# FPGA.net
KiCad netlist of a schematic drawn in Altium Designer
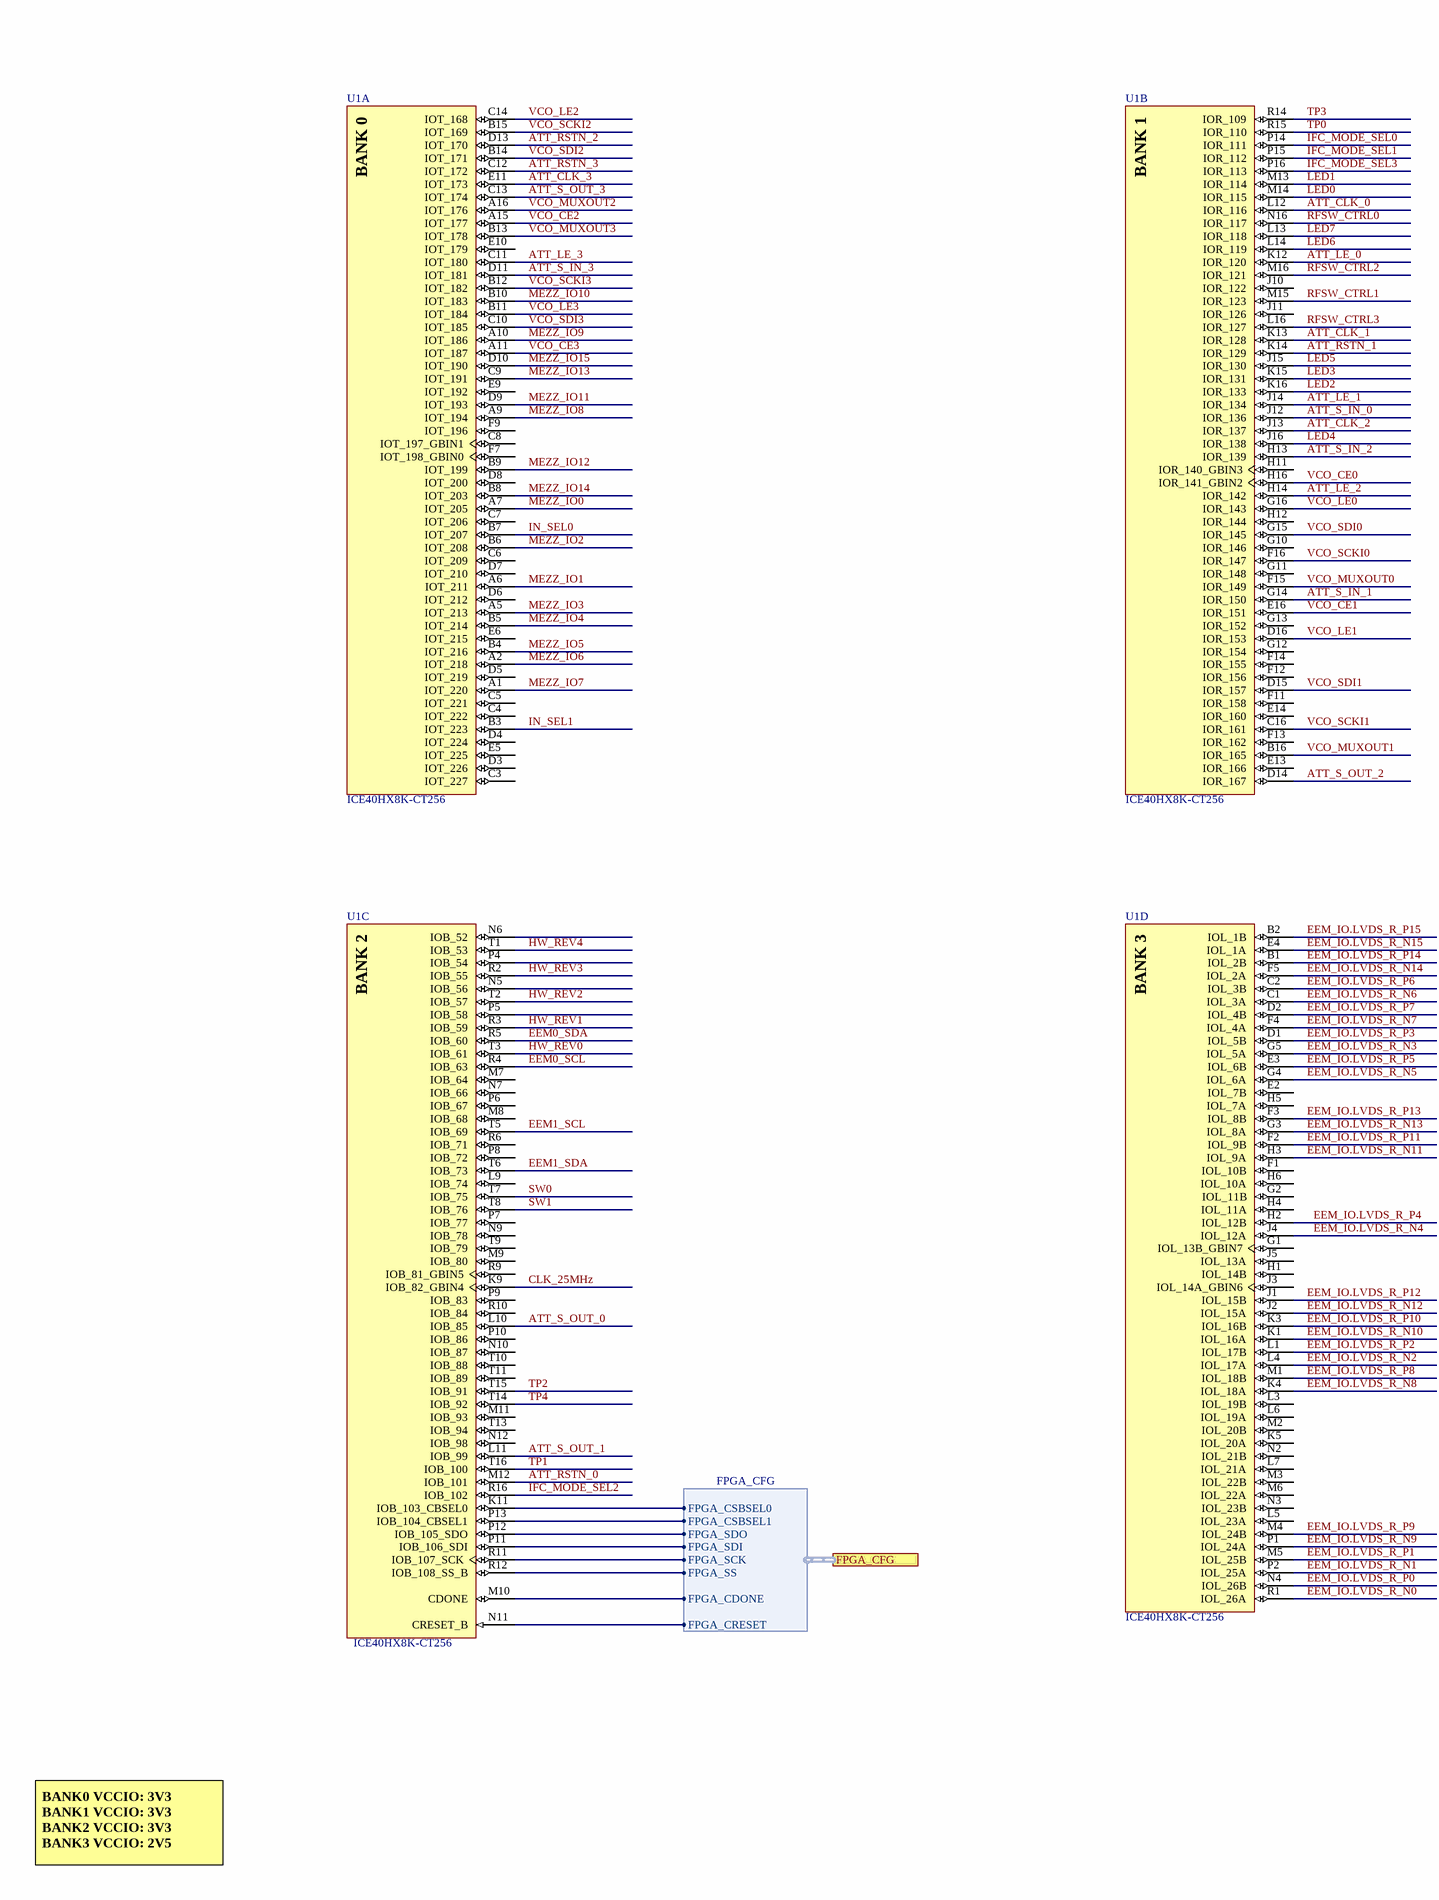
[diagram p0: FPGA.SchDoc, left]
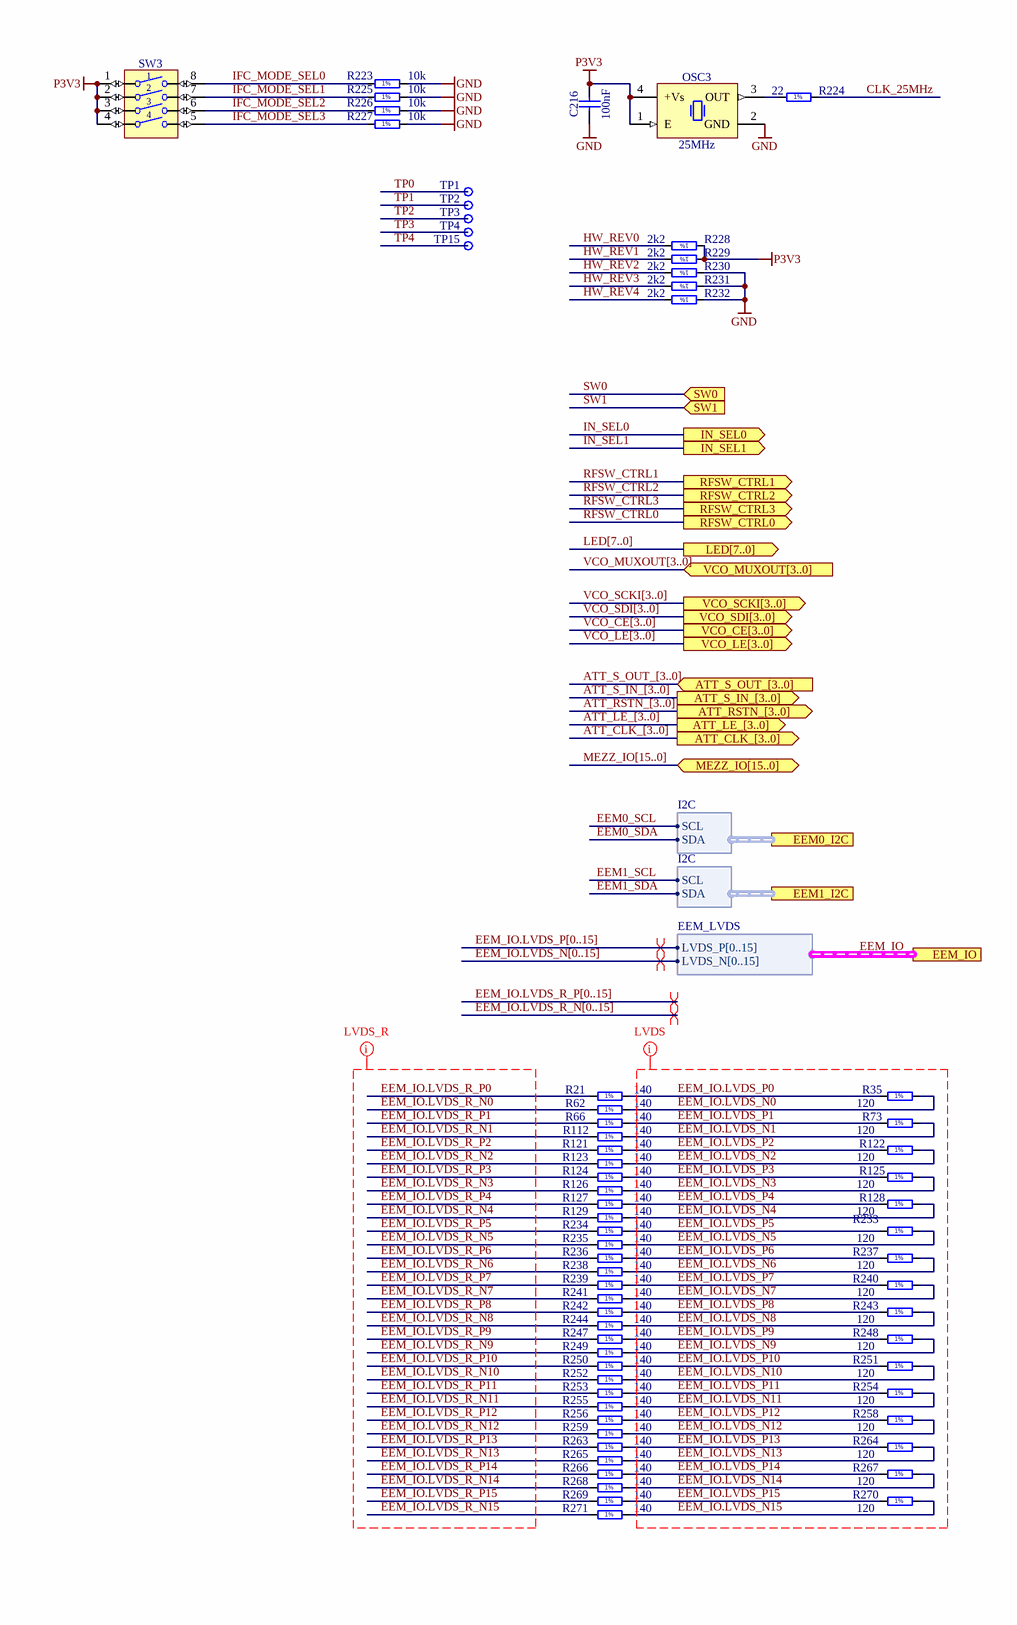
[diagram p1: FPGA.SchDoc, right]

(export (version "E")
  (design (tool "Eeschema 10.0.6"))
  (components
    (comp (ref "C216")
      (value "100nF")
      (footprint "CAPC1005X55N")
      (description "Non-polarised capacitor")
      (fields
        (field (name "PART NUMBER") "CC0402_100NF_16V_10%_X5R")
        (field (name "VOLTAGE") "16V")
        (field (name "AUTHOR") "CERN DEM JLC")
      )
      (libsource (lib "Capacitors") (part "Capacitor - non polarized"))
    )
    (comp (ref "OSC3")
      (value "25MHz")
      (footprint "OSC_IQD_CFPS-39")
      (description "Oscillator 4 pins 1=E 2=GND 3=OUT 4=+Vs")
      (fields
        (field (name "PART NUMBER") "OSC_25MHZ_IQD_LFSPXO025165")
        (field (name "MANUFACTURER") "IQD FREQUENCY PRODUCTS")
        (field (name "AUTHOR") "CERN DEM JLC")
      )
      (libsource (lib "ICs And Semiconductors") (part "Oscillator 1E 2GND 3OUT 4Vs"))
    )
    (comp (ref "R21")
      (value "140")
      (footprint "RESC0603X28N")
      (description "Resistor - 1%")
      (fields
        (field (name "PART NUMBER") "R0201_140R_1%_0.05W_200PPM")
        (field (name "POWER") "0.05W")
        (field (name "AUTHOR") "CERN DEM MR")
      )
      (libsource (lib "Resistors") (part "Resistor - 1%"))
    )
    (comp (ref "R35")
      (value "120")
      (footprint "RESC1005X40N")
      (description "Resistor - 1%")
      (fields
        (field (name "PART NUMBER") "R0402_120R_1%_0.0625W_100PPM")
        (field (name "POWER") "0.0625W")
        (field (name "AUTHOR") "CERN DEM JLC")
      )
      (libsource (lib "Resistors") (part "Resistor - 1%"))
    )
    (comp (ref "R62")
      (value "140")
      (footprint "RESC0603X28N")
      (description "Resistor - 1%")
      (fields
        (field (name "PART NUMBER") "R0201_140R_1%_0.05W_200PPM")
        (field (name "POWER") "0.05W")
        (field (name "AUTHOR") "CERN DEM MR")
      )
      (libsource (lib "Resistors") (part "Resistor - 1%"))
    )
    (comp (ref "R66")
      (value "140")
      (footprint "RESC0603X28N")
      (description "Resistor - 1%")
      (fields
        (field (name "PART NUMBER") "R0201_140R_1%_0.05W_200PPM")
        (field (name "POWER") "0.05W")
        (field (name "AUTHOR") "CERN DEM MR")
      )
      (libsource (lib "Resistors") (part "Resistor - 1%"))
    )
    (comp (ref "R73")
      (value "120")
      (footprint "RESC1005X40N")
      (description "Resistor - 1%")
      (fields
        (field (name "PART NUMBER") "R0402_120R_1%_0.0625W_100PPM")
        (field (name "POWER") "0.0625W")
        (field (name "AUTHOR") "CERN DEM JLC")
      )
      (libsource (lib "Resistors") (part "Resistor - 1%"))
    )
    (comp (ref "R112")
      (value "140")
      (footprint "RESC0603X28N")
      (description "Resistor - 1%")
      (fields
        (field (name "PART NUMBER") "R0201_140R_1%_0.05W_200PPM")
        (field (name "POWER") "0.05W")
        (field (name "AUTHOR") "CERN DEM MR")
      )
      (libsource (lib "Resistors") (part "Resistor - 1%"))
    )
    (comp (ref "R121")
      (value "140")
      (footprint "RESC0603X28N")
      (description "Resistor - 1%")
      (fields
        (field (name "PART NUMBER") "R0201_140R_1%_0.05W_200PPM")
        (field (name "POWER") "0.05W")
        (field (name "AUTHOR") "CERN DEM MR")
      )
      (libsource (lib "Resistors") (part "Resistor - 1%"))
    )
    (comp (ref "R122")
      (value "120")
      (footprint "RESC1005X40N")
      (description "Resistor - 1%")
      (fields
        (field (name "PART NUMBER") "R0402_120R_1%_0.0625W_100PPM")
        (field (name "POWER") "0.0625W")
        (field (name "AUTHOR") "CERN DEM JLC")
      )
      (libsource (lib "Resistors") (part "Resistor - 1%"))
    )
    (comp (ref "R123")
      (value "140")
      (footprint "RESC0603X28N")
      (description "Resistor - 1%")
      (fields
        (field (name "PART NUMBER") "R0201_140R_1%_0.05W_200PPM")
        (field (name "POWER") "0.05W")
        (field (name "AUTHOR") "CERN DEM MR")
      )
      (libsource (lib "Resistors") (part "Resistor - 1%"))
    )
    (comp (ref "R124")
      (value "140")
      (footprint "RESC0603X28N")
      (description "Resistor - 1%")
      (fields
        (field (name "PART NUMBER") "R0201_140R_1%_0.05W_200PPM")
        (field (name "POWER") "0.05W")
        (field (name "AUTHOR") "CERN DEM MR")
      )
      (libsource (lib "Resistors") (part "Resistor - 1%"))
    )
    (comp (ref "R125")
      (value "120")
      (footprint "RESC1005X40N")
      (description "Resistor - 1%")
      (fields
        (field (name "PART NUMBER") "R0402_120R_1%_0.0625W_100PPM")
        (field (name "POWER") "0.0625W")
        (field (name "AUTHOR") "CERN DEM JLC")
      )
      (libsource (lib "Resistors") (part "Resistor - 1%"))
    )
    (comp (ref "R126")
      (value "140")
      (footprint "RESC0603X28N")
      (description "Resistor - 1%")
      (fields
        (field (name "PART NUMBER") "R0201_140R_1%_0.05W_200PPM")
        (field (name "POWER") "0.05W")
        (field (name "AUTHOR") "CERN DEM MR")
      )
      (libsource (lib "Resistors") (part "Resistor - 1%"))
    )
    (comp (ref "R127")
      (value "140")
      (footprint "RESC0603X28N")
      (description "Resistor - 1%")
      (fields
        (field (name "PART NUMBER") "R0201_140R_1%_0.05W_200PPM")
        (field (name "POWER") "0.05W")
        (field (name "AUTHOR") "CERN DEM MR")
      )
      (libsource (lib "Resistors") (part "Resistor - 1%"))
    )
    (comp (ref "R128")
      (value "120")
      (footprint "RESC1005X40N")
      (description "Resistor - 1%")
      (fields
        (field (name "PART NUMBER") "R0402_120R_1%_0.0625W_100PPM")
        (field (name "POWER") "0.0625W")
        (field (name "AUTHOR") "CERN DEM JLC")
      )
      (libsource (lib "Resistors") (part "Resistor - 1%"))
    )
    (comp (ref "R129")
      (value "140")
      (footprint "RESC0603X28N")
      (description "Resistor - 1%")
      (fields
        (field (name "PART NUMBER") "R0201_140R_1%_0.05W_200PPM")
        (field (name "POWER") "0.05W")
        (field (name "AUTHOR") "CERN DEM MR")
      )
      (libsource (lib "Resistors") (part "Resistor - 1%"))
    )
    (comp (ref "R223")
      (value "10k")
      (footprint "RESC1005X40N")
      (description "Resistor - 1%")
      (fields
        (field (name "PART NUMBER") "R0402_10K_1%_0.0625W_100PPM")
        (field (name "POWER") "0.0625W")
        (field (name "AUTHOR") "CERN DEM JLC")
      )
      (libsource (lib "Resistors") (part "Resistor - 1%"))
    )
    (comp (ref "R224")
      (value "22")
      (footprint "RESC1005X40N")
      (description "Resistor - 1%")
      (fields
        (field (name "PART NUMBER") "R0402_22R_1%_0.0625W_100PPM")
        (field (name "POWER") "0.0625W")
        (field (name "AUTHOR") "CERN DEM JLC")
      )
      (libsource (lib "Resistors") (part "Resistor - 1%"))
    )
    (comp (ref "R225")
      (value "10k")
      (footprint "RESC1005X40N")
      (description "Resistor - 1%")
      (fields
        (field (name "PART NUMBER") "R0402_10K_1%_0.0625W_100PPM")
        (field (name "POWER") "0.0625W")
        (field (name "AUTHOR") "CERN DEM JLC")
      )
      (libsource (lib "Resistors") (part "Resistor - 1%"))
    )
    (comp (ref "R226")
      (value "10k")
      (footprint "RESC1005X40N")
      (description "Resistor - 1%")
      (fields
        (field (name "PART NUMBER") "R0402_10K_1%_0.0625W_100PPM")
        (field (name "POWER") "0.0625W")
        (field (name "AUTHOR") "CERN DEM JLC")
      )
      (libsource (lib "Resistors") (part "Resistor - 1%"))
    )
    (comp (ref "R227")
      (value "10k")
      (footprint "RESC1005X40N")
      (description "Resistor - 1%")
      (fields
        (field (name "PART NUMBER") "R0402_10K_1%_0.0625W_100PPM")
        (field (name "POWER") "0.0625W")
        (field (name "AUTHOR") "CERN DEM JLC")
      )
      (libsource (lib "Resistors") (part "Resistor - 1%"))
    )
    (comp (ref "R228")
      (value "2k2")
      (footprint "RESC1005X40N")
      (description "Resistor - 1%")
      (fields
        (field (name "PART NUMBER") "R0402_2K2_1%_0.0625W_100PPM")
        (field (name "POWER") "0.0625W")
        (field (name "AUTHOR") "CERN DEM JLC")
      )
      (libsource (lib "Resistors") (part "Resistor - 1%"))
    )
    (comp (ref "R229")
      (value "2k2")
      (footprint "RESC1005X40N")
      (description "Resistor - 1%")
      (fields
        (field (name "PART NUMBER") "R0402_2K2_1%_0.0625W_100PPM")
        (field (name "POWER") "0.0625W")
        (field (name "AUTHOR") "CERN DEM JLC")
      )
      (libsource (lib "Resistors") (part "Resistor - 1%"))
    )
    (comp (ref "R230")
      (value "2k2")
      (footprint "RESC1005X40N")
      (description "Resistor - 1%")
      (fields
        (field (name "PART NUMBER") "R0402_2K2_1%_0.0625W_100PPM")
        (field (name "POWER") "0.0625W")
        (field (name "AUTHOR") "CERN DEM JLC")
      )
      (libsource (lib "Resistors") (part "Resistor - 1%"))
    )
    (comp (ref "R231")
      (value "2k2")
      (footprint "RESC1005X40N")
      (description "Resistor - 1%")
      (fields
        (field (name "PART NUMBER") "R0402_2K2_1%_0.0625W_100PPM")
        (field (name "POWER") "0.0625W")
        (field (name "AUTHOR") "CERN DEM JLC")
      )
      (libsource (lib "Resistors") (part "Resistor - 1%"))
    )
    (comp (ref "R232")
      (value "2k2")
      (footprint "RESC1005X40N")
      (description "Resistor - 1%")
      (fields
        (field (name "PART NUMBER") "R0402_2K2_1%_0.0625W_100PPM")
        (field (name "POWER") "0.0625W")
        (field (name "AUTHOR") "CERN DEM JLC")
      )
      (libsource (lib "Resistors") (part "Resistor - 1%"))
    )
    (comp (ref "R233")
      (value "120")
      (footprint "RESC1005X40N")
      (description "Resistor - 1%")
      (fields
        (field (name "PART NUMBER") "R0402_120R_1%_0.0625W_100PPM")
        (field (name "POWER") "0.0625W")
        (field (name "AUTHOR") "CERN DEM JLC")
      )
      (libsource (lib "Resistors") (part "Resistor - 1%"))
    )
    (comp (ref "R234")
      (value "140")
      (footprint "RESC0603X28N")
      (description "Resistor - 1%")
      (fields
        (field (name "PART NUMBER") "R0201_140R_1%_0.05W_200PPM")
        (field (name "POWER") "0.05W")
        (field (name "AUTHOR") "CERN DEM MR")
      )
      (libsource (lib "Resistors") (part "Resistor - 1%"))
    )
    (comp (ref "R235")
      (value "140")
      (footprint "RESC0603X28N")
      (description "Resistor - 1%")
      (fields
        (field (name "PART NUMBER") "R0201_140R_1%_0.05W_200PPM")
        (field (name "POWER") "0.05W")
        (field (name "AUTHOR") "CERN DEM MR")
      )
      (libsource (lib "Resistors") (part "Resistor - 1%"))
    )
    (comp (ref "R236")
      (value "140")
      (footprint "RESC0603X28N")
      (description "Resistor - 1%")
      (fields
        (field (name "PART NUMBER") "R0201_140R_1%_0.05W_200PPM")
        (field (name "POWER") "0.05W")
        (field (name "AUTHOR") "CERN DEM MR")
      )
      (libsource (lib "Resistors") (part "Resistor - 1%"))
    )
    (comp (ref "R237")
      (value "120")
      (footprint "RESC1005X40N")
      (description "Resistor - 1%")
      (fields
        (field (name "PART NUMBER") "R0402_120R_1%_0.0625W_100PPM")
        (field (name "POWER") "0.0625W")
        (field (name "AUTHOR") "CERN DEM JLC")
      )
      (libsource (lib "Resistors") (part "Resistor - 1%"))
    )
    (comp (ref "R238")
      (value "140")
      (footprint "RESC0603X28N")
      (description "Resistor - 1%")
      (fields
        (field (name "PART NUMBER") "R0201_140R_1%_0.05W_200PPM")
        (field (name "POWER") "0.05W")
        (field (name "AUTHOR") "CERN DEM MR")
      )
      (libsource (lib "Resistors") (part "Resistor - 1%"))
    )
    (comp (ref "R239")
      (value "140")
      (footprint "RESC0603X28N")
      (description "Resistor - 1%")
      (fields
        (field (name "PART NUMBER") "R0201_140R_1%_0.05W_200PPM")
        (field (name "POWER") "0.05W")
        (field (name "AUTHOR") "CERN DEM MR")
      )
      (libsource (lib "Resistors") (part "Resistor - 1%"))
    )
    (comp (ref "R240")
      (value "120")
      (footprint "RESC1005X40N")
      (description "Resistor - 1%")
      (fields
        (field (name "PART NUMBER") "R0402_120R_1%_0.0625W_100PPM")
        (field (name "POWER") "0.0625W")
        (field (name "AUTHOR") "CERN DEM JLC")
      )
      (libsource (lib "Resistors") (part "Resistor - 1%"))
    )
    (comp (ref "R241")
      (value "140")
      (footprint "RESC0603X28N")
      (description "Resistor - 1%")
      (fields
        (field (name "PART NUMBER") "R0201_140R_1%_0.05W_200PPM")
        (field (name "POWER") "0.05W")
        (field (name "AUTHOR") "CERN DEM MR")
      )
      (libsource (lib "Resistors") (part "Resistor - 1%"))
    )
    (comp (ref "R242")
      (value "140")
      (footprint "RESC0603X28N")
      (description "Resistor - 1%")
      (fields
        (field (name "PART NUMBER") "R0201_140R_1%_0.05W_200PPM")
        (field (name "POWER") "0.05W")
        (field (name "AUTHOR") "CERN DEM MR")
      )
      (libsource (lib "Resistors") (part "Resistor - 1%"))
    )
    (comp (ref "R243")
      (value "120")
      (footprint "RESC1005X40N")
      (description "Resistor - 1%")
      (fields
        (field (name "PART NUMBER") "R0402_120R_1%_0.0625W_100PPM")
        (field (name "POWER") "0.0625W")
        (field (name "AUTHOR") "CERN DEM JLC")
      )
      (libsource (lib "Resistors") (part "Resistor - 1%"))
    )
    (comp (ref "R244")
      (value "140")
      (footprint "RESC0603X28N")
      (description "Resistor - 1%")
      (fields
        (field (name "PART NUMBER") "R0201_140R_1%_0.05W_200PPM")
        (field (name "POWER") "0.05W")
        (field (name "AUTHOR") "CERN DEM MR")
      )
      (libsource (lib "Resistors") (part "Resistor - 1%"))
    )
    (comp (ref "R247")
      (value "140")
      (footprint "RESC0603X28N")
      (description "Resistor - 1%")
      (fields
        (field (name "PART NUMBER") "R0201_140R_1%_0.05W_200PPM")
        (field (name "POWER") "0.05W")
        (field (name "AUTHOR") "CERN DEM MR")
      )
      (libsource (lib "Resistors") (part "Resistor - 1%"))
    )
    (comp (ref "R248")
      (value "120")
      (footprint "RESC1005X40N")
      (description "Resistor - 1%")
      (fields
        (field (name "PART NUMBER") "R0402_120R_1%_0.0625W_100PPM")
        (field (name "POWER") "0.0625W")
        (field (name "AUTHOR") "CERN DEM JLC")
      )
      (libsource (lib "Resistors") (part "Resistor - 1%"))
    )
    (comp (ref "R249")
      (value "140")
      (footprint "RESC0603X28N")
      (description "Resistor - 1%")
      (fields
        (field (name "PART NUMBER") "R0201_140R_1%_0.05W_200PPM")
        (field (name "POWER") "0.05W")
        (field (name "AUTHOR") "CERN DEM MR")
      )
      (libsource (lib "Resistors") (part "Resistor - 1%"))
    )
    (comp (ref "R250")
      (value "140")
      (footprint "RESC0603X28N")
      (description "Resistor - 1%")
      (fields
        (field (name "PART NUMBER") "R0201_140R_1%_0.05W_200PPM")
        (field (name "POWER") "0.05W")
        (field (name "AUTHOR") "CERN DEM MR")
      )
      (libsource (lib "Resistors") (part "Resistor - 1%"))
    )
    (comp (ref "R251")
      (value "120")
      (footprint "RESC1005X40N")
      (description "Resistor - 1%")
      (fields
        (field (name "PART NUMBER") "R0402_120R_1%_0.0625W_100PPM")
        (field (name "POWER") "0.0625W")
        (field (name "AUTHOR") "CERN DEM JLC")
      )
      (libsource (lib "Resistors") (part "Resistor - 1%"))
    )
    (comp (ref "R252")
      (value "140")
      (footprint "RESC0603X28N")
      (description "Resistor - 1%")
      (fields
        (field (name "PART NUMBER") "R0201_140R_1%_0.05W_200PPM")
        (field (name "POWER") "0.05W")
        (field (name "AUTHOR") "CERN DEM MR")
      )
      (libsource (lib "Resistors") (part "Resistor - 1%"))
    )
    (comp (ref "R253")
      (value "140")
      (footprint "RESC0603X28N")
      (description "Resistor - 1%")
      (fields
        (field (name "PART NUMBER") "R0201_140R_1%_0.05W_200PPM")
        (field (name "POWER") "0.05W")
        (field (name "AUTHOR") "CERN DEM MR")
      )
      (libsource (lib "Resistors") (part "Resistor - 1%"))
    )
    (comp (ref "R254")
      (value "120")
      (footprint "RESC1005X40N")
      (description "Resistor - 1%")
      (fields
        (field (name "PART NUMBER") "R0402_120R_1%_0.0625W_100PPM")
        (field (name "POWER") "0.0625W")
        (field (name "AUTHOR") "CERN DEM JLC")
      )
      (libsource (lib "Resistors") (part "Resistor - 1%"))
    )
    (comp (ref "R255")
      (value "140")
      (footprint "RESC0603X28N")
      (description "Resistor - 1%")
      (fields
        (field (name "PART NUMBER") "R0201_140R_1%_0.05W_200PPM")
        (field (name "POWER") "0.05W")
        (field (name "AUTHOR") "CERN DEM MR")
      )
      (libsource (lib "Resistors") (part "Resistor - 1%"))
    )
    (comp (ref "R256")
      (value "140")
      (footprint "RESC0603X28N")
      (description "Resistor - 1%")
      (fields
        (field (name "PART NUMBER") "R0201_140R_1%_0.05W_200PPM")
        (field (name "POWER") "0.05W")
        (field (name "AUTHOR") "CERN DEM MR")
      )
      (libsource (lib "Resistors") (part "Resistor - 1%"))
    )
    (comp (ref "R258")
      (value "120")
      (footprint "RESC1005X40N")
      (description "Resistor - 1%")
      (fields
        (field (name "PART NUMBER") "R0402_120R_1%_0.0625W_100PPM")
        (field (name "POWER") "0.0625W")
        (field (name "AUTHOR") "CERN DEM JLC")
      )
      (libsource (lib "Resistors") (part "Resistor - 1%"))
    )
    (comp (ref "R259")
      (value "140")
      (footprint "RESC0603X28N")
      (description "Resistor - 1%")
      (fields
        (field (name "PART NUMBER") "R0201_140R_1%_0.05W_200PPM")
        (field (name "POWER") "0.05W")
        (field (name "AUTHOR") "CERN DEM MR")
      )
      (libsource (lib "Resistors") (part "Resistor - 1%"))
    )
    (comp (ref "R263")
      (value "140")
      (footprint "RESC0603X28N")
      (description "Resistor - 1%")
      (fields
        (field (name "PART NUMBER") "R0201_140R_1%_0.05W_200PPM")
        (field (name "POWER") "0.05W")
        (field (name "AUTHOR") "CERN DEM MR")
      )
      (libsource (lib "Resistors") (part "Resistor - 1%"))
    )
    (comp (ref "R264")
      (value "120")
      (footprint "RESC1005X40N")
      (description "Resistor - 1%")
      (fields
        (field (name "PART NUMBER") "R0402_120R_1%_0.0625W_100PPM")
        (field (name "POWER") "0.0625W")
        (field (name "AUTHOR") "CERN DEM JLC")
      )
      (libsource (lib "Resistors") (part "Resistor - 1%"))
    )
    (comp (ref "R265")
      (value "140")
      (footprint "RESC0603X28N")
      (description "Resistor - 1%")
      (fields
        (field (name "PART NUMBER") "R0201_140R_1%_0.05W_200PPM")
        (field (name "POWER") "0.05W")
        (field (name "AUTHOR") "CERN DEM MR")
      )
      (libsource (lib "Resistors") (part "Resistor - 1%"))
    )
    (comp (ref "R266")
      (value "140")
      (footprint "RESC0603X28N")
      (description "Resistor - 1%")
      (fields
        (field (name "PART NUMBER") "R0201_140R_1%_0.05W_200PPM")
        (field (name "POWER") "0.05W")
        (field (name "AUTHOR") "CERN DEM MR")
      )
      (libsource (lib "Resistors") (part "Resistor - 1%"))
    )
    (comp (ref "R267")
      (value "120")
      (footprint "RESC1005X40N")
      (description "Resistor - 1%")
      (fields
        (field (name "PART NUMBER") "R0402_120R_1%_0.0625W_100PPM")
        (field (name "POWER") "0.0625W")
        (field (name "AUTHOR") "CERN DEM JLC")
      )
      (libsource (lib "Resistors") (part "Resistor - 1%"))
    )
    (comp (ref "R268")
      (value "140")
      (footprint "RESC0603X28N")
      (description "Resistor - 1%")
      (fields
        (field (name "PART NUMBER") "R0201_140R_1%_0.05W_200PPM")
        (field (name "POWER") "0.05W")
        (field (name "AUTHOR") "CERN DEM MR")
      )
      (libsource (lib "Resistors") (part "Resistor - 1%"))
    )
    (comp (ref "R269")
      (value "140")
      (footprint "RESC0603X28N")
      (description "Resistor - 1%")
      (fields
        (field (name "PART NUMBER") "R0201_140R_1%_0.05W_200PPM")
        (field (name "POWER") "0.05W")
        (field (name "AUTHOR") "CERN DEM MR")
      )
      (libsource (lib "Resistors") (part "Resistor - 1%"))
    )
    (comp (ref "R270")
      (value "120")
      (footprint "RESC1005X40N")
      (description "Resistor - 1%")
      (fields
        (field (name "PART NUMBER") "R0402_120R_1%_0.0625W_100PPM")
        (field (name "POWER") "0.0625W")
        (field (name "AUTHOR") "CERN DEM JLC")
      )
      (libsource (lib "Resistors") (part "Resistor - 1%"))
    )
    (comp (ref "R271")
      (value "140")
      (footprint "RESC0603X28N")
      (description "Resistor - 1%")
      (fields
        (field (name "PART NUMBER") "R0201_140R_1%_0.05W_200PPM")
        (field (name "POWER") "0.05W")
        (field (name "AUTHOR") "CERN DEM MR")
      )
      (libsource (lib "Resistors") (part "Resistor - 1%"))
    )
    (comp (ref "SW3")
      (value "Switch")
      (footprint "SW_TYCO_1571983-4")
      (description "4 Ways SPST DIP Switch")
      (fields
        (field (name "PART NUMBER") "SW_TYCO_1571983-4")
        (field (name "MANUFACTURER") "TYCO")
        (field (name "AUTHOR") "CERN DEM JLC")
      )
      (libsource (lib "Eletro-mechanical") (part "SW 4x SPST DIP Switch"))
    )
    (comp (ref "TP1")
      (value "Test Point")
      (footprint "TPS127")
      (fields (field (name "PART NUMBER") "SMD_PAD_1.27X1.27MM") (field (name "AUTHOR") "CERN DEM JLC"))
      (libsource (lib "Eletro-mechanical") (part "Test Point"))
    )
    (comp (ref "TP2")
      (value "Test Point")
      (footprint "TPS127")
      (fields (field (name "PART NUMBER") "SMD_PAD_1.27X1.27MM") (field (name "AUTHOR") "CERN DEM JLC"))
      (libsource (lib "Eletro-mechanical") (part "Test Point"))
    )
    (comp (ref "TP3")
      (value "Test Point")
      (footprint "TPS127")
      (fields (field (name "PART NUMBER") "SMD_PAD_1.27X1.27MM") (field (name "AUTHOR") "CERN DEM JLC"))
      (libsource (lib "Eletro-mechanical") (part "Test Point"))
    )
    (comp (ref "TP4")
      (value "Test Point")
      (footprint "TPS127")
      (fields (field (name "PART NUMBER") "SMD_PAD_1.27X1.27MM") (field (name "AUTHOR") "CERN DEM JLC"))
      (libsource (lib "Eletro-mechanical") (part "Test Point"))
    )
    (comp (ref "TP15")
      (value "Test Point")
      (footprint "TPS127")
      (fields (field (name "PART NUMBER") "SMD_PAD_1.27X1.27MM") (field (name "AUTHOR") "CERN DEM JLC"))
      (libsource (lib "Eletro-mechanical") (part "Test Point"))
    )
    (comp (ref "U1")
      (value "ICE40HX8K-CT256")
      (footprint "LATC-caBGA-256")
      (fields (field (name "MANUFACTURER") "Lattice Semiconductor"))
      (libsource (lib "Altium Content Vault") (part "LATC-HX8K-caBGA-256"))
    )
  )
  (nets
    (net (code "4") (name "/ATT_CLK_0") (class "Default")
      (node (ref "U1") (pin "L12") (pinfunction "IOR_116_L12") (pintype "bidirectional"))
    )
    (net (code "5") (name "/ATT_CLK_1") (class "Default")
      (node (ref "U1") (pin "K13") (pinfunction "IOR_128_K13") (pintype "bidirectional"))
    )
    (net (code "6") (name "/ATT_CLK_2") (class "Default")
      (node (ref "U1") (pin "J13") (pinfunction "IOR_137_J13") (pintype "bidirectional"))
    )
    (net (code "7") (name "/ATT_CLK_3") (class "Default")
      (node (ref "U1") (pin "E11") (pinfunction "IOT_173_E11") (pintype "bidirectional"))
    )
    (net (code "9") (name "/ATT_LE_0") (class "Default")
      (node (ref "U1") (pin "K12") (pinfunction "IOR_120_K12") (pintype "bidirectional"))
    )
    (net (code "10") (name "/ATT_LE_1") (class "Default")
      (node (ref "U1") (pin "J14") (pinfunction "IOR_134_J14") (pintype "bidirectional"))
    )
    (net (code "11") (name "/ATT_LE_2") (class "Default")
      (node (ref "U1") (pin "H14") (pinfunction "IOR_142_H14") (pintype "bidirectional"))
    )
    (net (code "12") (name "/ATT_LE_3") (class "Default")
      (node (ref "U1") (pin "C11") (pinfunction "IOT_180_C11") (pintype "bidirectional"))
    )
    (net (code "14") (name "/ATT_RSTN_0") (class "Default")
      (node (ref "U1") (pin "M12") (pinfunction "IOB_101_M12") (pintype "bidirectional"))
    )
    (net (code "15") (name "/ATT_RSTN_1") (class "Default")
      (node (ref "U1") (pin "K14") (pinfunction "IOR_129_K14") (pintype "bidirectional"))
    )
    (net (code "16") (name "/ATT_RSTN_2") (class "Default")
      (node (ref "U1") (pin "D13") (pinfunction "IOT_170_D13") (pintype "bidirectional"))
    )
    (net (code "17") (name "/ATT_RSTN_3") (class "Default")
      (node (ref "U1") (pin "C12") (pinfunction "IOT_172_C12") (pintype "bidirectional"))
    )
    (net (code "19") (name "/ATT_S_IN_0") (class "Default")
      (node (ref "U1") (pin "J12") (pinfunction "IOR_136_J12") (pintype "bidirectional"))
    )
    (net (code "20") (name "/ATT_S_IN_1") (class "Default")
      (node (ref "U1") (pin "G14") (pinfunction "IOR_150_G14") (pintype "bidirectional"))
    )
    (net (code "21") (name "/ATT_S_IN_2") (class "Default")
      (node (ref "U1") (pin "H13") (pinfunction "IOR_139_H13") (pintype "bidirectional"))
    )
    (net (code "22") (name "/ATT_S_IN_3") (class "Default")
      (node (ref "U1") (pin "D11") (pinfunction "IOT_181_D11") (pintype "bidirectional"))
    )
    (net (code "24") (name "/ATT_S_OUT_0") (class "Default")
      (node (ref "U1") (pin "L10") (pinfunction "IOB_85_L10") (pintype "bidirectional"))
    )
    (net (code "25") (name "/ATT_S_OUT_1") (class "Default")
      (node (ref "U1") (pin "L11") (pinfunction "IOB_99_L11") (pintype "bidirectional"))
    )
    (net (code "26") (name "/ATT_S_OUT_2") (class "Default")
      (node (ref "U1") (pin "D14") (pinfunction "IOR_167_D14") (pintype "bidirectional"))
    )
    (net (code "27") (name "/ATT_S_OUT_3") (class "Default")
      (node (ref "U1") (pin "C13") (pinfunction "IOT_174_C13") (pintype "bidirectional"))
    )
    (net (code "29") (name "/CLK_25MHz") (class "Default")
      (node (ref "R224") (pin "2") (pinfunction "2_2") (pintype "passive"))
      (node (ref "U1") (pin "K9") (pinfunction "IOB_82_GBIN4_K9") (pintype "bidirectional"))
    )
    (net (code "30") (name "/EEM0_SCL") (class "Default")
      (node (ref "U1") (pin "R4") (pinfunction "IOB_63_R4") (pintype "bidirectional"))
    )
    (net (code "31") (name "/EEM0_SDA") (class "Default")
      (node (ref "U1") (pin "R5") (pinfunction "IOB_60_R5") (pintype "bidirectional"))
    )
    (net (code "32") (name "/EEM1_SCL") (class "Default")
      (node (ref "U1") (pin "T5") (pinfunction "IOB_69_T5") (pintype "bidirectional"))
    )
    (net (code "33") (name "/EEM1_SDA") (class "Default")
      (node (ref "U1") (pin "T6") (pinfunction "IOB_73_T6") (pintype "bidirectional"))
    )
    (net (code "34") (name "/EEM_IO.LVDS_N0") (class "Default")
      (node (ref "R35") (pin "2") (pinfunction "2_2") (pintype "passive"))
      (node (ref "R62") (pin "2") (pinfunction "2_2") (pintype "passive"))
    )
    (net (code "35") (name "/EEM_IO.LVDS_N1") (class "Default")
      (node (ref "R112") (pin "2") (pinfunction "2_2") (pintype "passive"))
      (node (ref "R73") (pin "2") (pinfunction "2_2") (pintype "passive"))
    )
    (net (code "36") (name "/EEM_IO.LVDS_N2") (class "Default")
      (node (ref "R122") (pin "2") (pinfunction "2_2") (pintype "passive"))
      (node (ref "R123") (pin "2") (pinfunction "2_2") (pintype "passive"))
    )
    (net (code "37") (name "/EEM_IO.LVDS_N3") (class "Default")
      (node (ref "R125") (pin "2") (pinfunction "2_2") (pintype "passive"))
      (node (ref "R126") (pin "2") (pinfunction "2_2") (pintype "passive"))
    )
    (net (code "38") (name "/EEM_IO.LVDS_N4") (class "Default")
      (node (ref "R128") (pin "2") (pinfunction "2_2") (pintype "passive"))
      (node (ref "R129") (pin "2") (pinfunction "2_2") (pintype "passive"))
    )
    (net (code "39") (name "/EEM_IO.LVDS_N5") (class "Default")
      (node (ref "R233") (pin "2") (pinfunction "2_2") (pintype "passive"))
      (node (ref "R235") (pin "2") (pinfunction "2_2") (pintype "passive"))
    )
    (net (code "40") (name "/EEM_IO.LVDS_N6") (class "Default")
      (node (ref "R237") (pin "2") (pinfunction "2_2") (pintype "passive"))
      (node (ref "R238") (pin "2") (pinfunction "2_2") (pintype "passive"))
    )
    (net (code "41") (name "/EEM_IO.LVDS_N7") (class "Default")
      (node (ref "R240") (pin "2") (pinfunction "2_2") (pintype "passive"))
      (node (ref "R241") (pin "2") (pinfunction "2_2") (pintype "passive"))
    )
    (net (code "42") (name "/EEM_IO.LVDS_N8") (class "Default")
      (node (ref "R243") (pin "2") (pinfunction "2_2") (pintype "passive"))
      (node (ref "R244") (pin "2") (pinfunction "2_2") (pintype "passive"))
    )
    (net (code "43") (name "/EEM_IO.LVDS_N9") (class "Default")
      (node (ref "R248") (pin "2") (pinfunction "2_2") (pintype "passive"))
      (node (ref "R249") (pin "2") (pinfunction "2_2") (pintype "passive"))
    )
    (net (code "44") (name "/EEM_IO.LVDS_N10") (class "Default")
      (node (ref "R251") (pin "2") (pinfunction "2_2") (pintype "passive"))
      (node (ref "R252") (pin "2") (pinfunction "2_2") (pintype "passive"))
    )
    (net (code "45") (name "/EEM_IO.LVDS_N11") (class "Default")
      (node (ref "R254") (pin "2") (pinfunction "2_2") (pintype "passive"))
      (node (ref "R255") (pin "2") (pinfunction "2_2") (pintype "passive"))
    )
    (net (code "46") (name "/EEM_IO.LVDS_N12") (class "Default")
      (node (ref "R258") (pin "2") (pinfunction "2_2") (pintype "passive"))
      (node (ref "R259") (pin "2") (pinfunction "2_2") (pintype "passive"))
    )
    (net (code "47") (name "/EEM_IO.LVDS_N13") (class "Default")
      (node (ref "R264") (pin "2") (pinfunction "2_2") (pintype "passive"))
      (node (ref "R265") (pin "2") (pinfunction "2_2") (pintype "passive"))
    )
    (net (code "48") (name "/EEM_IO.LVDS_N14") (class "Default")
      (node (ref "R267") (pin "2") (pinfunction "2_2") (pintype "passive"))
      (node (ref "R268") (pin "2") (pinfunction "2_2") (pintype "passive"))
    )
    (net (code "49") (name "/EEM_IO.LVDS_N15") (class "Default")
      (node (ref "R270") (pin "2") (pinfunction "2_2") (pintype "passive"))
      (node (ref "R271") (pin "2") (pinfunction "2_2") (pintype "passive"))
    )
    (net (code "51") (name "/EEM_IO.LVDS_P0") (class "Default")
      (node (ref "R21") (pin "2") (pinfunction "2_2") (pintype "passive"))
      (node (ref "R35") (pin "1") (pinfunction "1_1") (pintype "passive"))
    )
    (net (code "52") (name "/EEM_IO.LVDS_P1") (class "Default")
      (node (ref "R66") (pin "2") (pinfunction "2_2") (pintype "passive"))
      (node (ref "R73") (pin "1") (pinfunction "1_1") (pintype "passive"))
    )
    (net (code "53") (name "/EEM_IO.LVDS_P2") (class "Default")
      (node (ref "R121") (pin "2") (pinfunction "2_2") (pintype "passive"))
      (node (ref "R122") (pin "1") (pinfunction "1_1") (pintype "passive"))
    )
    (net (code "54") (name "/EEM_IO.LVDS_P3") (class "Default")
      (node (ref "R124") (pin "2") (pinfunction "2_2") (pintype "passive"))
      (node (ref "R125") (pin "1") (pinfunction "1_1") (pintype "passive"))
    )
    (net (code "55") (name "/EEM_IO.LVDS_P4") (class "Default")
      (node (ref "R127") (pin "2") (pinfunction "2_2") (pintype "passive"))
      (node (ref "R128") (pin "1") (pinfunction "1_1") (pintype "passive"))
    )
    (net (code "56") (name "/EEM_IO.LVDS_P5") (class "Default")
      (node (ref "R233") (pin "1") (pinfunction "1_1") (pintype "passive"))
      (node (ref "R234") (pin "2") (pinfunction "2_2") (pintype "passive"))
    )
    (net (code "57") (name "/EEM_IO.LVDS_P6") (class "Default")
      (node (ref "R236") (pin "2") (pinfunction "2_2") (pintype "passive"))
      (node (ref "R237") (pin "1") (pinfunction "1_1") (pintype "passive"))
    )
    (net (code "58") (name "/EEM_IO.LVDS_P7") (class "Default")
      (node (ref "R239") (pin "2") (pinfunction "2_2") (pintype "passive"))
      (node (ref "R240") (pin "1") (pinfunction "1_1") (pintype "passive"))
    )
    (net (code "59") (name "/EEM_IO.LVDS_P8") (class "Default")
      (node (ref "R242") (pin "2") (pinfunction "2_2") (pintype "passive"))
      (node (ref "R243") (pin "1") (pinfunction "1_1") (pintype "passive"))
    )
    (net (code "60") (name "/EEM_IO.LVDS_P9") (class "Default")
      (node (ref "R247") (pin "2") (pinfunction "2_2") (pintype "passive"))
      (node (ref "R248") (pin "1") (pinfunction "1_1") (pintype "passive"))
    )
    (net (code "61") (name "/EEM_IO.LVDS_P10") (class "Default")
      (node (ref "R250") (pin "2") (pinfunction "2_2") (pintype "passive"))
      (node (ref "R251") (pin "1") (pinfunction "1_1") (pintype "passive"))
    )
    (net (code "62") (name "/EEM_IO.LVDS_P11") (class "Default")
      (node (ref "R253") (pin "2") (pinfunction "2_2") (pintype "passive"))
      (node (ref "R254") (pin "1") (pinfunction "1_1") (pintype "passive"))
    )
    (net (code "63") (name "/EEM_IO.LVDS_P12") (class "Default")
      (node (ref "R256") (pin "2") (pinfunction "2_2") (pintype "passive"))
      (node (ref "R258") (pin "1") (pinfunction "1_1") (pintype "passive"))
    )
    (net (code "64") (name "/EEM_IO.LVDS_P13") (class "Default")
      (node (ref "R263") (pin "2") (pinfunction "2_2") (pintype "passive"))
      (node (ref "R264") (pin "1") (pinfunction "1_1") (pintype "passive"))
    )
    (net (code "65") (name "/EEM_IO.LVDS_P14") (class "Default")
      (node (ref "R266") (pin "2") (pinfunction "2_2") (pintype "passive"))
      (node (ref "R267") (pin "1") (pinfunction "1_1") (pintype "passive"))
    )
    (net (code "66") (name "/EEM_IO.LVDS_P15") (class "Default")
      (node (ref "R269") (pin "2") (pinfunction "2_2") (pintype "passive"))
      (node (ref "R270") (pin "1") (pinfunction "1_1") (pintype "passive"))
    )
    (net (code "68") (name "/EEM_IO.LVDS_R_N0") (class "Default")
      (node (ref "R62") (pin "1") (pinfunction "1_1") (pintype "passive"))
      (node (ref "U1") (pin "R1") (pinfunction "IOL_26A_R1") (pintype "bidirectional"))
    )
    (net (code "69") (name "/EEM_IO.LVDS_R_N1") (class "Default")
      (node (ref "R112") (pin "1") (pinfunction "1_1") (pintype "passive"))
      (node (ref "U1") (pin "P2") (pinfunction "IOL_25A_P2") (pintype "bidirectional"))
    )
    (net (code "70") (name "/EEM_IO.LVDS_R_N2") (class "Default")
      (node (ref "R123") (pin "1") (pinfunction "1_1") (pintype "passive"))
      (node (ref "U1") (pin "L4") (pinfunction "IOL_17A_L4") (pintype "bidirectional"))
    )
    (net (code "71") (name "/EEM_IO.LVDS_R_N3") (class "Default")
      (node (ref "R126") (pin "1") (pinfunction "1_1") (pintype "passive"))
      (node (ref "U1") (pin "G5") (pinfunction "IOL_5A_G5") (pintype "bidirectional"))
    )
    (net (code "72") (name "/EEM_IO.LVDS_R_N4") (class "Default")
      (node (ref "R129") (pin "1") (pinfunction "1_1") (pintype "passive"))
      (node (ref "U1") (pin "J4") (pinfunction "IOL_12A_J4") (pintype "bidirectional"))
    )
    (net (code "73") (name "/EEM_IO.LVDS_R_N5") (class "Default")
      (node (ref "R235") (pin "1") (pinfunction "1_1") (pintype "passive"))
      (node (ref "U1") (pin "G4") (pinfunction "IOL_6A_G4") (pintype "bidirectional"))
    )
    (net (code "74") (name "/EEM_IO.LVDS_R_N6") (class "Default")
      (node (ref "R238") (pin "1") (pinfunction "1_1") (pintype "passive"))
      (node (ref "U1") (pin "C1") (pinfunction "IOL_3A_C1") (pintype "bidirectional"))
    )
    (net (code "75") (name "/EEM_IO.LVDS_R_N7") (class "Default")
      (node (ref "R241") (pin "1") (pinfunction "1_1") (pintype "passive"))
      (node (ref "U1") (pin "F4") (pinfunction "IOL_4A_F4") (pintype "bidirectional"))
    )
    (net (code "76") (name "/EEM_IO.LVDS_R_N8") (class "Default")
      (node (ref "R244") (pin "1") (pinfunction "1_1") (pintype "passive"))
      (node (ref "U1") (pin "K4") (pinfunction "IOL_18A_K4") (pintype "bidirectional"))
    )
    (net (code "77") (name "/EEM_IO.LVDS_R_N9") (class "Default")
      (node (ref "R249") (pin "1") (pinfunction "1_1") (pintype "passive"))
      (node (ref "U1") (pin "P1") (pinfunction "IOL_24A_P1") (pintype "bidirectional"))
    )
    (net (code "78") (name "/EEM_IO.LVDS_R_N10") (class "Default")
      (node (ref "R252") (pin "1") (pinfunction "1_1") (pintype "passive"))
      (node (ref "U1") (pin "K1") (pinfunction "IOL_16A_K1") (pintype "bidirectional"))
    )
    (net (code "79") (name "/EEM_IO.LVDS_R_N11") (class "Default")
      (node (ref "R255") (pin "1") (pinfunction "1_1") (pintype "passive"))
      (node (ref "U1") (pin "H3") (pinfunction "IOL_9A_H3") (pintype "bidirectional"))
    )
    (net (code "80") (name "/EEM_IO.LVDS_R_N12") (class "Default")
      (node (ref "R259") (pin "1") (pinfunction "1_1") (pintype "passive"))
      (node (ref "U1") (pin "J2") (pinfunction "IOL_15A_J2") (pintype "bidirectional"))
    )
    (net (code "81") (name "/EEM_IO.LVDS_R_N13") (class "Default")
      (node (ref "R265") (pin "1") (pinfunction "1_1") (pintype "passive"))
      (node (ref "U1") (pin "G3") (pinfunction "IOL_8A_G3") (pintype "bidirectional"))
    )
    (net (code "82") (name "/EEM_IO.LVDS_R_N14") (class "Default")
      (node (ref "R268") (pin "1") (pinfunction "1_1") (pintype "passive"))
      (node (ref "U1") (pin "F5") (pinfunction "IOL_2A_F5") (pintype "bidirectional"))
    )
    (net (code "83") (name "/EEM_IO.LVDS_R_N15") (class "Default")
      (node (ref "R271") (pin "1") (pinfunction "1_1") (pintype "passive"))
      (node (ref "U1") (pin "E4") (pinfunction "IOL_1A_E4") (pintype "bidirectional"))
    )
    (net (code "85") (name "/EEM_IO.LVDS_R_P0") (class "Default")
      (node (ref "R21") (pin "1") (pinfunction "1_1") (pintype "passive"))
      (node (ref "U1") (pin "N4") (pinfunction "IOL_26B_N4") (pintype "bidirectional"))
    )
    (net (code "86") (name "/EEM_IO.LVDS_R_P1") (class "Default")
      (node (ref "R66") (pin "1") (pinfunction "1_1") (pintype "passive"))
      (node (ref "U1") (pin "M5") (pinfunction "IOL_25B_M5") (pintype "bidirectional"))
    )
    (net (code "87") (name "/EEM_IO.LVDS_R_P2") (class "Default")
      (node (ref "R121") (pin "1") (pinfunction "1_1") (pintype "passive"))
      (node (ref "U1") (pin "L1") (pinfunction "IOL_17B_L1") (pintype "bidirectional"))
    )
    (net (code "88") (name "/EEM_IO.LVDS_R_P3") (class "Default")
      (node (ref "R124") (pin "1") (pinfunction "1_1") (pintype "passive"))
      (node (ref "U1") (pin "D1") (pinfunction "IOL_5B_D1") (pintype "bidirectional"))
    )
    (net (code "89") (name "/EEM_IO.LVDS_R_P4") (class "Default")
      (node (ref "R127") (pin "1") (pinfunction "1_1") (pintype "passive"))
      (node (ref "U1") (pin "H2") (pinfunction "IOL_12B_H2") (pintype "bidirectional"))
    )
    (net (code "90") (name "/EEM_IO.LVDS_R_P5") (class "Default")
      (node (ref "R234") (pin "1") (pinfunction "1_1") (pintype "passive"))
      (node (ref "U1") (pin "E3") (pinfunction "IOL_6B_E3") (pintype "bidirectional"))
    )
    (net (code "91") (name "/EEM_IO.LVDS_R_P6") (class "Default")
      (node (ref "R236") (pin "1") (pinfunction "1_1") (pintype "passive"))
      (node (ref "U1") (pin "C2") (pinfunction "IOL_3B_C2") (pintype "bidirectional"))
    )
    (net (code "92") (name "/EEM_IO.LVDS_R_P7") (class "Default")
      (node (ref "R239") (pin "1") (pinfunction "1_1") (pintype "passive"))
      (node (ref "U1") (pin "D2") (pinfunction "IOL_4B_D2") (pintype "bidirectional"))
    )
    (net (code "93") (name "/EEM_IO.LVDS_R_P8") (class "Default")
      (node (ref "R242") (pin "1") (pinfunction "1_1") (pintype "passive"))
      (node (ref "U1") (pin "M1") (pinfunction "IOL_18B_M1") (pintype "bidirectional"))
    )
    (net (code "94") (name "/EEM_IO.LVDS_R_P9") (class "Default")
      (node (ref "R247") (pin "1") (pinfunction "1_1") (pintype "passive"))
      (node (ref "U1") (pin "M4") (pinfunction "IOL_24B_M4") (pintype "bidirectional"))
    )
    (net (code "95") (name "/EEM_IO.LVDS_R_P10") (class "Default")
      (node (ref "R250") (pin "1") (pinfunction "1_1") (pintype "passive"))
      (node (ref "U1") (pin "K3") (pinfunction "IOL_16B_K3") (pintype "bidirectional"))
    )
    (net (code "96") (name "/EEM_IO.LVDS_R_P11") (class "Default")
      (node (ref "R253") (pin "1") (pinfunction "1_1") (pintype "passive"))
      (node (ref "U1") (pin "F2") (pinfunction "IOL_9B_F2") (pintype "bidirectional"))
    )
    (net (code "97") (name "/EEM_IO.LVDS_R_P12") (class "Default")
      (node (ref "R256") (pin "1") (pinfunction "1_1") (pintype "passive"))
      (node (ref "U1") (pin "J1") (pinfunction "IOL_15B_J1") (pintype "bidirectional"))
    )
    (net (code "98") (name "/EEM_IO.LVDS_R_P13") (class "Default")
      (node (ref "R263") (pin "1") (pinfunction "1_1") (pintype "passive"))
      (node (ref "U1") (pin "F3") (pinfunction "IOL_8B_F3") (pintype "bidirectional"))
    )
    (net (code "99") (name "/EEM_IO.LVDS_R_P14") (class "Default")
      (node (ref "R266") (pin "1") (pinfunction "1_1") (pintype "passive"))
      (node (ref "U1") (pin "B1") (pinfunction "IOL_2B_B1") (pintype "bidirectional"))
    )
    (net (code "100") (name "/EEM_IO.LVDS_R_P15") (class "Default")
      (node (ref "R269") (pin "1") (pinfunction "1_1") (pintype "passive"))
      (node (ref "U1") (pin "B2") (pinfunction "IOL_1B_B2") (pintype "bidirectional"))
    )
    (net (code "103") (name "/FPGA_CDONE") (class "Default")
      (node (ref "U1") (pin "M10") (pinfunction "CDONE_M10") (pintype "bidirectional"))
    )
    (net (code "104") (name "/FPGA_CRESET") (class "Default")
      (node (ref "U1") (pin "N11") (pinfunction "CRESET_B_N11") (pintype "input"))
    )
    (net (code "105") (name "/FPGA_CSBSEL0") (class "Default")
      (node (ref "U1") (pin "K11") (pinfunction "IOB_103_CBSEL0_K11") (pintype "bidirectional"))
    )
    (net (code "106") (name "/FPGA_CSBSEL1") (class "Default")
      (node (ref "U1") (pin "P13") (pinfunction "IOB_104_CBSEL1_P13") (pintype "bidirectional"))
    )
    (net (code "107") (name "/FPGA_SCK") (class "Default")
      (node (ref "U1") (pin "R11") (pinfunction "IOB_107_SCK_R11") (pintype "bidirectional"))
    )
    (net (code "108") (name "/FPGA_SDI") (class "Default")
      (node (ref "U1") (pin "P11") (pinfunction "IOB_106_SDI_P11") (pintype "bidirectional"))
    )
    (net (code "109") (name "/FPGA_SDO") (class "Default")
      (node (ref "U1") (pin "P12") (pinfunction "IOB_105_SDO_P12") (pintype "bidirectional"))
    )
    (net (code "110") (name "/FPGA_SS") (class "Default")
      (node (ref "U1") (pin "R12") (pinfunction "IOB_108_SS_B_R12") (pintype "bidirectional"))
    )
    (net (code "111") (name "/HW_REV0") (class "Default")
      (node (ref "R228") (pin "2") (pinfunction "2_2") (pintype "passive"))
      (node (ref "U1") (pin "T3") (pinfunction "IOB_61_T3") (pintype "bidirectional"))
    )
    (net (code "112") (name "/HW_REV1") (class "Default")
      (node (ref "R229") (pin "2") (pinfunction "2_2") (pintype "passive"))
      (node (ref "U1") (pin "R3") (pinfunction "IOB_59_R3") (pintype "bidirectional"))
    )
    (net (code "113") (name "/HW_REV2") (class "Default")
      (node (ref "R230") (pin "2") (pinfunction "2_2") (pintype "passive"))
      (node (ref "U1") (pin "T2") (pinfunction "IOB_57_T2") (pintype "bidirectional"))
    )
    (net (code "114") (name "/HW_REV3") (class "Default")
      (node (ref "R231") (pin "2") (pinfunction "2_2") (pintype "passive"))
      (node (ref "U1") (pin "R2") (pinfunction "IOB_55_R2") (pintype "bidirectional"))
    )
    (net (code "115") (name "/HW_REV4") (class "Default")
      (node (ref "R232") (pin "2") (pinfunction "2_2") (pintype "passive"))
      (node (ref "U1") (pin "T1") (pinfunction "IOB_53_T1") (pintype "bidirectional"))
    )
    (net (code "116") (name "/IFC_MODE_SEL0") (class "Default")
      (node (ref "R223") (pin "1") (pinfunction "1_1") (pintype "passive"))
      (node (ref "SW3") (pin "8") (pinfunction "8_8") (pintype "bidirectional"))
      (node (ref "U1") (pin "P14") (pinfunction "IOR_111_P14") (pintype "bidirectional"))
    )
    (net (code "117") (name "/IFC_MODE_SEL1") (class "Default")
      (node (ref "R225") (pin "1") (pinfunction "1_1") (pintype "passive"))
      (node (ref "SW3") (pin "7") (pinfunction "7_7") (pintype "bidirectional"))
      (node (ref "U1") (pin "P15") (pinfunction "IOR_112_P15") (pintype "bidirectional"))
    )
    (net (code "118") (name "/IFC_MODE_SEL2") (class "Default")
      (node (ref "R226") (pin "1") (pinfunction "1_1") (pintype "passive"))
      (node (ref "SW3") (pin "6") (pinfunction "6_6") (pintype "bidirectional"))
      (node (ref "U1") (pin "R16") (pinfunction "IOB_102_R16") (pintype "bidirectional"))
    )
    (net (code "119") (name "/IFC_MODE_SEL3") (class "Default")
      (node (ref "R227") (pin "1") (pinfunction "1_1") (pintype "passive"))
      (node (ref "SW3") (pin "5") (pinfunction "5_5") (pintype "bidirectional"))
      (node (ref "U1") (pin "P16") (pinfunction "IOR_113_P16") (pintype "bidirectional"))
    )
    (net (code "120") (name "/IN_SEL0") (class "Default")
      (node (ref "U1") (pin "B7") (pinfunction "IOT_207_B7") (pintype "bidirectional"))
    )
    (net (code "121") (name "/IN_SEL1") (class "Default")
      (node (ref "U1") (pin "B3") (pinfunction "IOT_223_B3") (pintype "bidirectional"))
    )
    (net (code "122") (name "/LED0") (class "Default")
      (node (ref "U1") (pin "M14") (pinfunction "IOR_115_M14") (pintype "bidirectional"))
    )
    (net (code "123") (name "/LED1") (class "Default")
      (node (ref "U1") (pin "M13") (pinfunction "IOR_114_M13") (pintype "bidirectional"))
    )
    (net (code "124") (name "/LED2") (class "Default")
      (node (ref "U1") (pin "K16") (pinfunction "IOR_133_K16") (pintype "bidirectional"))
    )
    (net (code "125") (name "/LED3") (class "Default")
      (node (ref "U1") (pin "K15") (pinfunction "IOR_131_K15") (pintype "bidirectional"))
    )
    (net (code "126") (name "/LED4") (class "Default")
      (node (ref "U1") (pin "J16") (pinfunction "IOR_138_J16") (pintype "bidirectional"))
    )
    (net (code "127") (name "/LED5") (class "Default")
      (node (ref "U1") (pin "J15") (pinfunction "IOR_130_J15") (pintype "bidirectional"))
    )
    (net (code "128") (name "/LED6") (class "Default")
      (node (ref "U1") (pin "L14") (pinfunction "IOR_119_L14") (pintype "bidirectional"))
    )
    (net (code "129") (name "/LED7") (class "Default")
      (node (ref "U1") (pin "L13") (pinfunction "IOR_118_L13") (pintype "bidirectional"))
    )
    (net (code "131") (name "/MEZZ_IO0") (class "Default")
      (node (ref "U1") (pin "A7") (pinfunction "IOT_205_A7") (pintype "bidirectional"))
    )
    (net (code "132") (name "/MEZZ_IO1") (class "Default")
      (node (ref "U1") (pin "A6") (pinfunction "IOT_211_A6") (pintype "bidirectional"))
    )
    (net (code "133") (name "/MEZZ_IO2") (class "Default")
      (node (ref "U1") (pin "B6") (pinfunction "IOT_208_B6") (pintype "bidirectional"))
    )
    (net (code "134") (name "/MEZZ_IO3") (class "Default")
      (node (ref "U1") (pin "A5") (pinfunction "IOT_213_A5") (pintype "bidirectional"))
    )
    (net (code "135") (name "/MEZZ_IO4") (class "Default")
      (node (ref "U1") (pin "B5") (pinfunction "IOT_214_B5") (pintype "bidirectional"))
    )
    (net (code "136") (name "/MEZZ_IO5") (class "Default")
      (node (ref "U1") (pin "B4") (pinfunction "IOT_216_B4") (pintype "bidirectional"))
    )
    (net (code "137") (name "/MEZZ_IO6") (class "Default")
      (node (ref "U1") (pin "A2") (pinfunction "IOT_218_A2") (pintype "bidirectional"))
    )
    (net (code "138") (name "/MEZZ_IO7") (class "Default")
      (node (ref "U1") (pin "A1") (pinfunction "IOT_220_A1") (pintype "bidirectional"))
    )
    (net (code "139") (name "/MEZZ_IO8") (class "Default")
      (node (ref "U1") (pin "A9") (pinfunction "IOT_194_A9") (pintype "bidirectional"))
    )
    (net (code "140") (name "/MEZZ_IO9") (class "Default")
      (node (ref "U1") (pin "A10") (pinfunction "IOT_186_A10") (pintype "bidirectional"))
    )
    (net (code "141") (name "/MEZZ_IO10") (class "Default")
      (node (ref "U1") (pin "B10") (pinfunction "IOT_183_B10") (pintype "bidirectional"))
    )
    (net (code "142") (name "/MEZZ_IO11") (class "Default")
      (node (ref "U1") (pin "D9") (pinfunction "IOT_193_D9") (pintype "bidirectional"))
    )
    (net (code "143") (name "/MEZZ_IO12") (class "Default")
      (node (ref "U1") (pin "B9") (pinfunction "IOT_199_B9") (pintype "bidirectional"))
    )
    (net (code "144") (name "/MEZZ_IO13") (class "Default")
      (node (ref "U1") (pin "C9") (pinfunction "IOT_191_C9") (pintype "bidirectional"))
    )
    (net (code "145") (name "/MEZZ_IO14") (class "Default")
      (node (ref "U1") (pin "B8") (pinfunction "IOT_203_B8") (pintype "bidirectional"))
    )
    (net (code "146") (name "/MEZZ_IO15") (class "Default")
      (node (ref "U1") (pin "D10") (pinfunction "IOT_190_D10") (pintype "bidirectional"))
    )
    (net (code "148") (name "/RFSW_CTRL0") (class "Default")
      (node (ref "U1") (pin "N16") (pinfunction "IOR_117_N16") (pintype "bidirectional"))
    )
    (net (code "149") (name "/RFSW_CTRL1") (class "Default")
      (node (ref "U1") (pin "M15") (pinfunction "IOR_123_M15") (pintype "bidirectional"))
    )
    (net (code "150") (name "/RFSW_CTRL2") (class "Default")
      (node (ref "U1") (pin "M16") (pinfunction "IOR_121_M16") (pintype "bidirectional"))
    )
    (net (code "151") (name "/RFSW_CTRL3") (class "Default")
      (node (ref "U1") (pin "L16") (pinfunction "IOR_127_L16") (pintype "bidirectional"))
    )
    (net (code "152") (name "/SW0") (class "Default")
      (node (ref "U1") (pin "T7") (pinfunction "IOB_75_T7") (pintype "bidirectional"))
    )
    (net (code "153") (name "/SW1") (class "Default")
      (node (ref "U1") (pin "T8") (pinfunction "IOB_76_T8") (pintype "bidirectional"))
    )
    (net (code "154") (name "/TP0") (class "Default")
      (node (ref "TP1") (pin "1") (pinfunction "1_1") (pintype "bidirectional"))
      (node (ref "U1") (pin "R15") (pinfunction "IOR_110_R15") (pintype "bidirectional"))
    )
    (net (code "155") (name "/TP1") (class "Default")
      (node (ref "TP2") (pin "1") (pinfunction "1_1") (pintype "bidirectional"))
      (node (ref "U1") (pin "T16") (pinfunction "IOB_100_T16") (pintype "bidirectional"))
    )
    (net (code "156") (name "/TP2") (class "Default")
      (node (ref "TP3") (pin "1") (pinfunction "1_1") (pintype "bidirectional"))
      (node (ref "U1") (pin "T15") (pinfunction "IOB_91_T15") (pintype "bidirectional"))
    )
    (net (code "157") (name "/TP3") (class "Default")
      (node (ref "TP4") (pin "1") (pinfunction "1_1") (pintype "bidirectional"))
      (node (ref "U1") (pin "R14") (pinfunction "IOR_109_R14") (pintype "bidirectional"))
    )
    (net (code "158") (name "/TP4") (class "Default")
      (node (ref "TP15") (pin "1") (pinfunction "1_1") (pintype "bidirectional"))
      (node (ref "U1") (pin "T14") (pinfunction "IOB_92_T14") (pintype "bidirectional"))
    )
    (net (code "159") (name "/VCO_CE0") (class "Default")
      (node (ref "U1") (pin "H16") (pinfunction "IOR_141_GBIN2_H16") (pintype "bidirectional"))
    )
    (net (code "160") (name "/VCO_CE1") (class "Default")
      (node (ref "U1") (pin "E16") (pinfunction "IOR_151_E16") (pintype "bidirectional"))
    )
    (net (code "161") (name "/VCO_CE2") (class "Default")
      (node (ref "U1") (pin "A15") (pinfunction "IOT_177_A15") (pintype "bidirectional"))
    )
    (net (code "162") (name "/VCO_CE3") (class "Default")
      (node (ref "U1") (pin "A11") (pinfunction "IOT_187_A11") (pintype "bidirectional"))
    )
    (net (code "164") (name "/VCO_LE0") (class "Default")
      (node (ref "U1") (pin "G16") (pinfunction "IOR_143_G16") (pintype "bidirectional"))
    )
    (net (code "165") (name "/VCO_LE1") (class "Default")
      (node (ref "U1") (pin "D16") (pinfunction "IOR_153_D16") (pintype "bidirectional"))
    )
    (net (code "166") (name "/VCO_LE2") (class "Default")
      (node (ref "U1") (pin "C14") (pinfunction "IOT_168_C14") (pintype "bidirectional"))
    )
    (net (code "167") (name "/VCO_LE3") (class "Default")
      (node (ref "U1") (pin "B11") (pinfunction "IOT_184_B11") (pintype "bidirectional"))
    )
    (net (code "169") (name "/VCO_MUXOUT0") (class "Default")
      (node (ref "U1") (pin "F15") (pinfunction "IOR_149_F15") (pintype "bidirectional"))
    )
    (net (code "170") (name "/VCO_MUXOUT1") (class "Default")
      (node (ref "U1") (pin "B16") (pinfunction "IOR_165_B16") (pintype "bidirectional"))
    )
    (net (code "171") (name "/VCO_MUXOUT2") (class "Default")
      (node (ref "U1") (pin "A16") (pinfunction "IOT_176_A16") (pintype "bidirectional"))
    )
    (net (code "172") (name "/VCO_MUXOUT3") (class "Default")
      (node (ref "U1") (pin "B13") (pinfunction "IOT_178_B13") (pintype "bidirectional"))
    )
    (net (code "174") (name "/VCO_SCKI0") (class "Default")
      (node (ref "U1") (pin "F16") (pinfunction "IOR_147_F16") (pintype "bidirectional"))
    )
    (net (code "175") (name "/VCO_SCKI1") (class "Default")
      (node (ref "U1") (pin "C16") (pinfunction "IOR_161_C16") (pintype "bidirectional"))
    )
    (net (code "176") (name "/VCO_SCKI2") (class "Default")
      (node (ref "U1") (pin "B15") (pinfunction "IOT_169_B15") (pintype "bidirectional"))
    )
    (net (code "177") (name "/VCO_SCKI3") (class "Default")
      (node (ref "U1") (pin "B12") (pinfunction "IOT_182_B12") (pintype "bidirectional"))
    )
    (net (code "179") (name "/VCO_SDI0") (class "Default")
      (node (ref "U1") (pin "G15") (pinfunction "IOR_145_G15") (pintype "bidirectional"))
    )
    (net (code "180") (name "/VCO_SDI1") (class "Default")
      (node (ref "U1") (pin "D15") (pinfunction "IOR_157_D15") (pintype "bidirectional"))
    )
    (net (code "181") (name "/VCO_SDI2") (class "Default")
      (node (ref "U1") (pin "B14") (pinfunction "IOT_171_B14") (pintype "bidirectional"))
    )
    (net (code "182") (name "/VCO_SDI3") (class "Default")
      (node (ref "U1") (pin "C10") (pinfunction "IOT_185_C10") (pintype "bidirectional"))
    )
    (net (code "186") (name "GND") (class "Default")
      (node (ref "C216") (pin "1") (pinfunction "1_1") (pintype "passive"))
      (node (ref "OSC3") (pin "2") (pinfunction "GND_2") (pintype "power_in"))
      (node (ref "R223") (pin "2") (pinfunction "2_2") (pintype "passive"))
      (node (ref "R225") (pin "2") (pinfunction "2_2") (pintype "passive"))
      (node (ref "R226") (pin "2") (pinfunction "2_2") (pintype "passive"))
      (node (ref "R227") (pin "2") (pinfunction "2_2") (pintype "passive"))
      (node (ref "R230") (pin "1") (pinfunction "1_1") (pintype "passive"))
      (node (ref "R231") (pin "1") (pinfunction "1_1") (pintype "passive"))
      (node (ref "R232") (pin "1") (pinfunction "1_1") (pintype "passive"))
    )
    (net (code "187") (name "Net-(OSC3-OUT)") (class "Default")
      (node (ref "OSC3") (pin "3") (pinfunction "OUT_3") (pintype "output"))
      (node (ref "R224") (pin "1") (pinfunction "1_1") (pintype "passive"))
    )
    (net (code "188") (name "P3V3") (class "Default")
      (node (ref "C216") (pin "2") (pinfunction "2_2") (pintype "passive"))
      (node (ref "OSC3") (pin "1") (pinfunction "E_1") (pintype "input"))
      (node (ref "OSC3") (pin "4") (pinfunction "+Vs_4") (pintype "power_in"))
      (node (ref "R228") (pin "1") (pinfunction "1_1") (pintype "passive"))
      (node (ref "R229") (pin "1") (pinfunction "1_1") (pintype "passive"))
      (node (ref "SW3") (pin "1") (pinfunction "1_1") (pintype "bidirectional"))
      (node (ref "SW3") (pin "2") (pinfunction "2_2") (pintype "bidirectional"))
      (node (ref "SW3") (pin "3") (pinfunction "3_3") (pintype "bidirectional"))
      (node (ref "SW3") (pin "4") (pinfunction "4_4") (pintype "bidirectional"))
    )
    (net (code "189") (name "unconnected-(U1A-IOT_179-PadE10)") (class "Default")
      (node (ref "U1") (pin "E10") (pinfunction "IOT_179_E10") (pintype "bidirectional"))
    )
    (net (code "190") (name "unconnected-(U1A-IOT_192-PadE9)") (class "Default")
      (node (ref "U1") (pin "E9") (pinfunction "IOT_192_E9") (pintype "bidirectional"))
    )
    (net (code "191") (name "unconnected-(U1A-IOT_196-PadF9)") (class "Default")
      (node (ref "U1") (pin "F9") (pinfunction "IOT_196_F9") (pintype "bidirectional"))
    )
    (net (code "192") (name "unconnected-(U1A-IOT_197_GBIN1-PadC8)") (class "Default")
      (node (ref "U1") (pin "C8") (pinfunction "IOT_197_GBIN1_C8") (pintype "bidirectional"))
    )
    (net (code "193") (name "unconnected-(U1A-IOT_198_GBIN0-PadF7)") (class "Default")
      (node (ref "U1") (pin "F7") (pinfunction "IOT_198_GBIN0_F7") (pintype "bidirectional"))
    )
    (net (code "194") (name "unconnected-(U1A-IOT_200-PadD8)") (class "Default")
      (node (ref "U1") (pin "D8") (pinfunction "IOT_200_D8") (pintype "bidirectional"))
    )
    (net (code "195") (name "unconnected-(U1A-IOT_206-PadC7)") (class "Default")
      (node (ref "U1") (pin "C7") (pinfunction "IOT_206_C7") (pintype "bidirectional"))
    )
    (net (code "196") (name "unconnected-(U1A-IOT_209-PadC6)") (class "Default")
      (node (ref "U1") (pin "C6") (pinfunction "IOT_209_C6") (pintype "bidirectional"))
    )
    (net (code "197") (name "unconnected-(U1A-IOT_210-PadD7)") (class "Default")
      (node (ref "U1") (pin "D7") (pinfunction "IOT_210_D7") (pintype "bidirectional"))
    )
    (net (code "198") (name "unconnected-(U1A-IOT_212-PadD6)") (class "Default")
      (node (ref "U1") (pin "D6") (pinfunction "IOT_212_D6") (pintype "bidirectional"))
    )
    (net (code "199") (name "unconnected-(U1A-IOT_215-PadE6)") (class "Default")
      (node (ref "U1") (pin "E6") (pinfunction "IOT_215_E6") (pintype "bidirectional"))
    )
    (net (code "200") (name "unconnected-(U1A-IOT_219-PadD5)") (class "Default")
      (node (ref "U1") (pin "D5") (pinfunction "IOT_219_D5") (pintype "bidirectional"))
    )
    (net (code "201") (name "unconnected-(U1A-IOT_221-PadC5)") (class "Default")
      (node (ref "U1") (pin "C5") (pinfunction "IOT_221_C5") (pintype "bidirectional"))
    )
    (net (code "202") (name "unconnected-(U1A-IOT_222-PadC4)") (class "Default")
      (node (ref "U1") (pin "C4") (pinfunction "IOT_222_C4") (pintype "bidirectional"))
    )
    (net (code "203") (name "unconnected-(U1A-IOT_224-PadD4)") (class "Default")
      (node (ref "U1") (pin "D4") (pinfunction "IOT_224_D4") (pintype "bidirectional"))
    )
    (net (code "204") (name "unconnected-(U1A-IOT_225-PadE5)") (class "Default")
      (node (ref "U1") (pin "E5") (pinfunction "IOT_225_E5") (pintype "bidirectional"))
    )
    (net (code "205") (name "unconnected-(U1A-IOT_226-PadD3)") (class "Default")
      (node (ref "U1") (pin "D3") (pinfunction "IOT_226_D3") (pintype "bidirectional"))
    )
    (net (code "206") (name "unconnected-(U1A-IOT_227-PadC3)") (class "Default")
      (node (ref "U1") (pin "C3") (pinfunction "IOT_227_C3") (pintype "bidirectional"))
    )
    (net (code "207") (name "unconnected-(U1B-IOR_122-PadJ10)") (class "Default")
      (node (ref "U1") (pin "J10") (pinfunction "IOR_122_J10") (pintype "bidirectional"))
    )
    (net (code "208") (name "unconnected-(U1B-IOR_126-PadJ11)") (class "Default")
      (node (ref "U1") (pin "J11") (pinfunction "IOR_126_J11") (pintype "bidirectional"))
    )
    (net (code "209") (name "unconnected-(U1B-IOR_140_GBIN3-PadH11)") (class "Default")
      (node (ref "U1") (pin "H11") (pinfunction "IOR_140_GBIN3_H11") (pintype "bidirectional"))
    )
    (net (code "210") (name "unconnected-(U1B-IOR_144-PadH12)") (class "Default")
      (node (ref "U1") (pin "H12") (pinfunction "IOR_144_H12") (pintype "bidirectional"))
    )
    (net (code "211") (name "unconnected-(U1B-IOR_146-PadG10)") (class "Default")
      (node (ref "U1") (pin "G10") (pinfunction "IOR_146_G10") (pintype "bidirectional"))
    )
    (net (code "212") (name "unconnected-(U1B-IOR_148-PadG11)") (class "Default")
      (node (ref "U1") (pin "G11") (pinfunction "IOR_148_G11") (pintype "bidirectional"))
    )
    (net (code "213") (name "unconnected-(U1B-IOR_152-PadG13)") (class "Default")
      (node (ref "U1") (pin "G13") (pinfunction "IOR_152_G13") (pintype "bidirectional"))
    )
    (net (code "214") (name "unconnected-(U1B-IOR_154-PadG12)") (class "Default")
      (node (ref "U1") (pin "G12") (pinfunction "IOR_154_G12") (pintype "bidirectional"))
    )
    (net (code "215") (name "unconnected-(U1B-IOR_155-PadF14)") (class "Default")
      (node (ref "U1") (pin "F14") (pinfunction "IOR_155_F14") (pintype "bidirectional"))
    )
    (net (code "216") (name "unconnected-(U1B-IOR_156-PadF12)") (class "Default")
      (node (ref "U1") (pin "F12") (pinfunction "IOR_156_F12") (pintype "bidirectional"))
    )
    (net (code "217") (name "unconnected-(U1B-IOR_158-PadF11)") (class "Default")
      (node (ref "U1") (pin "F11") (pinfunction "IOR_158_F11") (pintype "bidirectional"))
    )
    (net (code "218") (name "unconnected-(U1B-IOR_160-PadE14)") (class "Default")
      (node (ref "U1") (pin "E14") (pinfunction "IOR_160_E14") (pintype "bidirectional"))
    )
    (net (code "219") (name "unconnected-(U1B-IOR_162-PadF13)") (class "Default")
      (node (ref "U1") (pin "F13") (pinfunction "IOR_162_F13") (pintype "bidirectional"))
    )
    (net (code "220") (name "unconnected-(U1B-IOR_166-PadE13)") (class "Default")
      (node (ref "U1") (pin "E13") (pinfunction "IOR_166_E13") (pintype "bidirectional"))
    )
    (net (code "221") (name "unconnected-(U1C-IOB_52-PadN6)") (class "Default")
      (node (ref "U1") (pin "N6") (pinfunction "IOB_52_N6") (pintype "bidirectional"))
    )
    (net (code "222") (name "unconnected-(U1C-IOB_54-PadP4)") (class "Default")
      (node (ref "U1") (pin "P4") (pinfunction "IOB_54_P4") (pintype "bidirectional"))
    )
    (net (code "223") (name "unconnected-(U1C-IOB_56-PadN5)") (class "Default")
      (node (ref "U1") (pin "N5") (pinfunction "IOB_56_N5") (pintype "bidirectional"))
    )
    (net (code "224") (name "unconnected-(U1C-IOB_58-PadP5)") (class "Default")
      (node (ref "U1") (pin "P5") (pinfunction "IOB_58_P5") (pintype "bidirectional"))
    )
    (net (code "225") (name "unconnected-(U1C-IOB_64-PadM7)") (class "Default")
      (node (ref "U1") (pin "M7") (pinfunction "IOB_64_M7") (pintype "bidirectional"))
    )
    (net (code "226") (name "unconnected-(U1C-IOB_66-PadN7)") (class "Default")
      (node (ref "U1") (pin "N7") (pinfunction "IOB_66_N7") (pintype "bidirectional"))
    )
    (net (code "227") (name "unconnected-(U1C-IOB_67-PadP6)") (class "Default")
      (node (ref "U1") (pin "P6") (pinfunction "IOB_67_P6") (pintype "bidirectional"))
    )
    (net (code "228") (name "unconnected-(U1C-IOB_68-PadM8)") (class "Default")
      (node (ref "U1") (pin "M8") (pinfunction "IOB_68_M8") (pintype "bidirectional"))
    )
    (net (code "229") (name "unconnected-(U1C-IOB_71-PadR6)") (class "Default")
      (node (ref "U1") (pin "R6") (pinfunction "IOB_71_R6") (pintype "bidirectional"))
    )
    (net (code "230") (name "unconnected-(U1C-IOB_72-PadP8)") (class "Default")
      (node (ref "U1") (pin "P8") (pinfunction "IOB_72_P8") (pintype "bidirectional"))
    )
    (net (code "231") (name "unconnected-(U1C-IOB_74-PadL9)") (class "Default")
      (node (ref "U1") (pin "L9") (pinfunction "IOB_74_L9") (pintype "bidirectional"))
    )
    (net (code "232") (name "unconnected-(U1C-IOB_77-PadP7)") (class "Default")
      (node (ref "U1") (pin "P7") (pinfunction "IOB_77_P7") (pintype "bidirectional"))
    )
    (net (code "233") (name "unconnected-(U1C-IOB_78-PadN9)") (class "Default")
      (node (ref "U1") (pin "N9") (pinfunction "IOB_78_N9") (pintype "bidirectional"))
    )
    (net (code "234") (name "unconnected-(U1C-IOB_79-PadT9)") (class "Default")
      (node (ref "U1") (pin "T9") (pinfunction "IOB_79_T9") (pintype "bidirectional"))
    )
    (net (code "235") (name "unconnected-(U1C-IOB_80-PadM9)") (class "Default")
      (node (ref "U1") (pin "M9") (pinfunction "IOB_80_M9") (pintype "bidirectional"))
    )
    (net (code "236") (name "unconnected-(U1C-IOB_81_GBIN5-PadR9)") (class "Default")
      (node (ref "U1") (pin "R9") (pinfunction "IOB_81_GBIN5_R9") (pintype "bidirectional"))
    )
    (net (code "237") (name "unconnected-(U1C-IOB_83-PadP9)") (class "Default")
      (node (ref "U1") (pin "P9") (pinfunction "IOB_83_P9") (pintype "bidirectional"))
    )
    (net (code "238") (name "unconnected-(U1C-IOB_84-PadR10)") (class "Default")
      (node (ref "U1") (pin "R10") (pinfunction "IOB_84_R10") (pintype "bidirectional"))
    )
    (net (code "239") (name "unconnected-(U1C-IOB_86-PadP10)") (class "Default")
      (node (ref "U1") (pin "P10") (pinfunction "IOB_86_P10") (pintype "bidirectional"))
    )
    (net (code "240") (name "unconnected-(U1C-IOB_87-PadN10)") (class "Default")
      (node (ref "U1") (pin "N10") (pinfunction "IOB_87_N10") (pintype "bidirectional"))
    )
    (net (code "241") (name "unconnected-(U1C-IOB_88-PadT10)") (class "Default")
      (node (ref "U1") (pin "T10") (pinfunction "IOB_88_T10") (pintype "bidirectional"))
    )
    (net (code "242") (name "unconnected-(U1C-IOB_89-PadT11)") (class "Default")
      (node (ref "U1") (pin "T11") (pinfunction "IOB_89_T11") (pintype "bidirectional"))
    )
    (net (code "243") (name "unconnected-(U1C-IOB_93-PadM11)") (class "Default")
      (node (ref "U1") (pin "M11") (pinfunction "IOB_93_M11") (pintype "bidirectional"))
    )
    (net (code "244") (name "unconnected-(U1C-IOB_94-PadT13)") (class "Default")
      (node (ref "U1") (pin "T13") (pinfunction "IOB_94_T13") (pintype "bidirectional"))
    )
    (net (code "245") (name "unconnected-(U1C-IOB_98-PadN12)") (class "Default")
      (node (ref "U1") (pin "N12") (pinfunction "IOB_98_N12") (pintype "bidirectional"))
    )
    (net (code "246") (name "unconnected-(U1D-IOL_7A-PadH5)") (class "Default")
      (node (ref "U1") (pin "H5") (pinfunction "IOL_7A_H5") (pintype "bidirectional"))
    )
    (net (code "247") (name "unconnected-(U1D-IOL_7B-PadE2)") (class "Default")
      (node (ref "U1") (pin "E2") (pinfunction "IOL_7B_E2") (pintype "bidirectional"))
    )
    (net (code "248") (name "unconnected-(U1D-IOL_10A-PadH6)") (class "Default")
      (node (ref "U1") (pin "H6") (pinfunction "IOL_10A_H6") (pintype "bidirectional"))
    )
    (net (code "249") (name "unconnected-(U1D-IOL_10B-PadF1)") (class "Default")
      (node (ref "U1") (pin "F1") (pinfunction "IOL_10B_F1") (pintype "bidirectional"))
    )
    (net (code "250") (name "unconnected-(U1D-IOL_11A-PadH4)") (class "Default")
      (node (ref "U1") (pin "H4") (pinfunction "IOL_11A_H4") (pintype "bidirectional"))
    )
    (net (code "251") (name "unconnected-(U1D-IOL_11B-PadG2)") (class "Default")
      (node (ref "U1") (pin "G2") (pinfunction "IOL_11B_G2") (pintype "bidirectional"))
    )
    (net (code "252") (name "unconnected-(U1D-IOL_13A-PadJ5)") (class "Default")
      (node (ref "U1") (pin "J5") (pinfunction "IOL_13A_J5") (pintype "bidirectional"))
    )
    (net (code "253") (name "unconnected-(U1D-IOL_13B_GBIN7-PadG1)") (class "Default")
      (node (ref "U1") (pin "G1") (pinfunction "IOL_13B_GBIN7_G1") (pintype "bidirectional"))
    )
    (net (code "254") (name "unconnected-(U1D-IOL_14A_GBIN6-PadJ3)") (class "Default")
      (node (ref "U1") (pin "J3") (pinfunction "IOL_14A_GBIN6_J3") (pintype "bidirectional"))
    )
    (net (code "255") (name "unconnected-(U1D-IOL_14B-PadH1)") (class "Default")
      (node (ref "U1") (pin "H1") (pinfunction "IOL_14B_H1") (pintype "bidirectional"))
    )
    (net (code "256") (name "unconnected-(U1D-IOL_19A-PadL6)") (class "Default")
      (node (ref "U1") (pin "L6") (pinfunction "IOL_19A_L6") (pintype "bidirectional"))
    )
    (net (code "257") (name "unconnected-(U1D-IOL_19B-PadL3)") (class "Default")
      (node (ref "U1") (pin "L3") (pinfunction "IOL_19B_L3") (pintype "bidirectional"))
    )
    (net (code "258") (name "unconnected-(U1D-IOL_20A-PadK5)") (class "Default")
      (node (ref "U1") (pin "K5") (pinfunction "IOL_20A_K5") (pintype "bidirectional"))
    )
    (net (code "259") (name "unconnected-(U1D-IOL_20B-PadM2)") (class "Default")
      (node (ref "U1") (pin "M2") (pinfunction "IOL_20B_M2") (pintype "bidirectional"))
    )
    (net (code "260") (name "unconnected-(U1D-IOL_21A-PadL7)") (class "Default")
      (node (ref "U1") (pin "L7") (pinfunction "IOL_21A_L7") (pintype "bidirectional"))
    )
    (net (code "261") (name "unconnected-(U1D-IOL_21B-PadN2)") (class "Default")
      (node (ref "U1") (pin "N2") (pinfunction "IOL_21B_N2") (pintype "bidirectional"))
    )
    (net (code "262") (name "unconnected-(U1D-IOL_22A-PadM6)") (class "Default")
      (node (ref "U1") (pin "M6") (pinfunction "IOL_22A_M6") (pintype "bidirectional"))
    )
    (net (code "263") (name "unconnected-(U1D-IOL_22B-PadM3)") (class "Default")
      (node (ref "U1") (pin "M3") (pinfunction "IOL_22B_M3") (pintype "bidirectional"))
    )
    (net (code "264") (name "unconnected-(U1D-IOL_23A-PadL5)") (class "Default")
      (node (ref "U1") (pin "L5") (pinfunction "IOL_23A_L5") (pintype "bidirectional"))
    )
    (net (code "265") (name "unconnected-(U1D-IOL_23B-PadN3)") (class "Default")
      (node (ref "U1") (pin "N3") (pinfunction "IOL_23B_N3") (pintype "bidirectional"))
    )
  )
)
